# AtTiny85.net
KiCad netlist of a schematic drawn in EAGLE
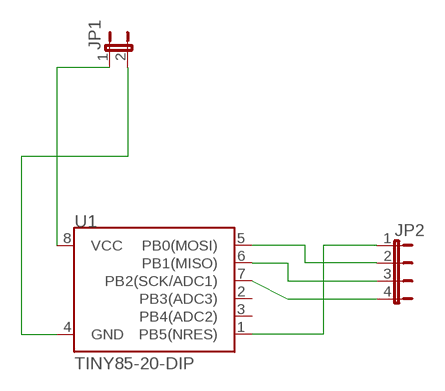
[diagram p0: schematic, sheet 1]

(export (version "E")
  (design (tool "Eeschema 10.0.6"))
  (components
    (comp (ref "JP1")
      (value "JP1E")
      (footprint "eagle-import:JP1")
      (libsource (lib "eagle-import") (part "JP1E"))
    )
    (comp (ref "JP2")
      (value "JP4E")
      (footprint "eagle-import:JP4")
      (libsource (lib "eagle-import") (part "JP4E"))
    )
    (comp (ref "U1")
      (value "TINY85-20-DIP")
      (footprint "eagle-import:DIP08")
      (libsource (lib "eagle-import") (part "ATTINY45TINY85-20-DIP"))
    )
  )
  (nets
    (net (code "1") (name "Net-(U1-GND)") (class "Default")
      (node (ref "JP1") (pin "2") (pinfunction "2_2") (pintype "passive"))
      (node (ref "U1") (pin "4") (pinfunction "GND_4") (pintype "bidirectional"))
    )
    (net (code "2") (name "Net-(U1-PB0(MOSI))") (class "Default")
      (node (ref "JP2") (pin "2") (pinfunction "2_2") (pintype "passive"))
      (node (ref "U1") (pin "5") (pinfunction "PB0(MOSI)_5") (pintype "bidirectional"))
    )
    (net (code "3") (name "Net-(U1-PB1(MISO))") (class "Default")
      (node (ref "JP2") (pin "3") (pinfunction "3_3") (pintype "passive"))
      (node (ref "U1") (pin "6") (pinfunction "PB1(MISO)_6") (pintype "bidirectional"))
    )
    (net (code "4") (name "Net-(U1-PB2(SCK{slash}ADC1))") (class "Default")
      (node (ref "JP2") (pin "4") (pinfunction "4_4") (pintype "passive"))
      (node (ref "U1") (pin "7") (pinfunction "PB2(SCK/ADC1)_7") (pintype "bidirectional"))
    )
    (net (code "5") (name "Net-(U1-PB5(NRES))") (class "Default")
      (node (ref "JP2") (pin "1") (pinfunction "1_1") (pintype "passive"))
      (node (ref "U1") (pin "1") (pinfunction "PB5(NRES)_1") (pintype "bidirectional"))
    )
    (net (code "6") (name "Net-(U1-VCC)") (class "Default")
      (node (ref "JP1") (pin "1") (pinfunction "1_1") (pintype "passive"))
      (node (ref "U1") (pin "8") (pinfunction "VCC_8") (pintype "bidirectional"))
    )
    (net (code "7") (name "unconnected-(U1-PB3(ADC3)-Pad2)") (class "Default")
      (node (ref "U1") (pin "2") (pinfunction "PB3(ADC3)_2") (pintype "bidirectional"))
    )
    (net (code "8") (name "unconnected-(U1-PB4(ADC2)-Pad3)") (class "Default")
      (node (ref "U1") (pin "3") (pinfunction "PB4(ADC2)_3") (pintype "bidirectional"))
    )
  )
)
